# Callisto_Header_Test_Board_All_On.net
KiCad netlist of a schematic drawn in EAGLE
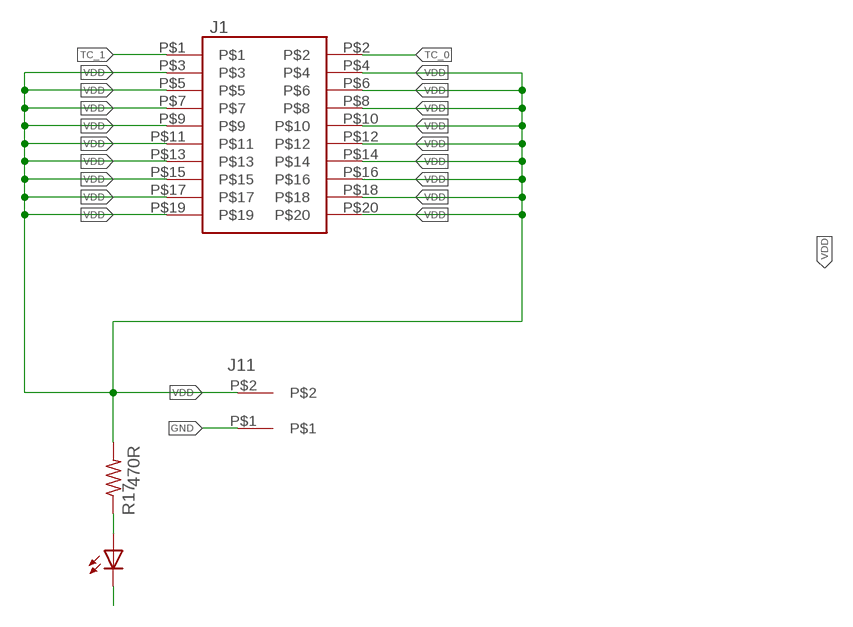
[diagram p0: schematic, sheet 1]

(export (version "E")
  (design (tool "Eeschema 10.0.6"))
  (components
    (comp (ref "J1")
      (value "20-pos")
      (footprint "eagle-import:2_X_10_.1_INCH")
      (fields (field (name "PARTNO") "67996-420HLF"))
      (libsource (lib "eagle-import") (part "2_X_10_HEADER_GENERIC"))
    )
    (comp (ref "J11")
      (value "2-pos")
      (footprint "eagle-import:2_3.81MM_PITCH")
      (fields (field (name "PARTNO") "691322310002"))
      (libsource (lib "eagle-import") (part "3.81MM_1_X_2_RT_ANGLE_PLUG_HEADER"))
    )
    (comp (ref "LED17")
      (value "Green")
      (footprint "eagle-import:0805")
      (fields (field (name "PARTNO") "LG R971-KN-1"))
      (libsource (lib "eagle-import") (part "LED_0805_GREEN"))
    )
    (comp (ref "R17")
      (value "470R")
      (footprint "eagle-import:0402")
      (libsource (lib "eagle-import") (part "R_0402"))
    )
  )
  (nets
    (net (code "1") (name "GND") (class "Default")
      (node (ref "J11") (pin "P$1") (pinfunction "P$1_P$1") (pintype "bidirectional"))
      (node (ref "LED17") (pin "2") (pinfunction "C_2") (pintype "passive"))
    )
    (net (code "2") (name "Net-(LED17-A)") (class "Default")
      (node (ref "LED17") (pin "1") (pinfunction "A_1") (pintype "passive"))
      (node (ref "R17") (pin "P$1") (pinfunction "1_P$1") (pintype "passive"))
    )
    (net (code "3") (name "TC_0") (class "Default")
      (node (ref "J1") (pin "P$2") (pinfunction "P$2_P$2") (pintype "bidirectional"))
    )
    (net (code "4") (name "TC_1") (class "Default")
      (node (ref "J1") (pin "P$1") (pinfunction "P$1_P$1") (pintype "bidirectional"))
    )
    (net (code "5") (name "VDD") (class "Default")
      (node (ref "J1") (pin "P$10") (pinfunction "P$10_P$10") (pintype "bidirectional"))
      (node (ref "J1") (pin "P$11") (pinfunction "P$11_P$11") (pintype "bidirectional"))
      (node (ref "J1") (pin "P$12") (pinfunction "P$12_P$12") (pintype "bidirectional"))
      (node (ref "J1") (pin "P$13") (pinfunction "P$13_P$13") (pintype "bidirectional"))
      (node (ref "J1") (pin "P$14") (pinfunction "P$14_P$14") (pintype "bidirectional"))
      (node (ref "J1") (pin "P$15") (pinfunction "P$15_P$15") (pintype "bidirectional"))
      (node (ref "J1") (pin "P$16") (pinfunction "P$16_P$16") (pintype "bidirectional"))
      (node (ref "J1") (pin "P$17") (pinfunction "P$17_P$17") (pintype "bidirectional"))
      (node (ref "J1") (pin "P$18") (pinfunction "P$18_P$18") (pintype "bidirectional"))
      (node (ref "J1") (pin "P$19") (pinfunction "P$19_P$19") (pintype "bidirectional"))
      (node (ref "J1") (pin "P$20") (pinfunction "P$20_P$20") (pintype "bidirectional"))
      (node (ref "J1") (pin "P$3") (pinfunction "P$3_P$3") (pintype "bidirectional"))
      (node (ref "J1") (pin "P$4") (pinfunction "P$4_P$4") (pintype "bidirectional"))
      (node (ref "J1") (pin "P$5") (pinfunction "P$5_P$5") (pintype "bidirectional"))
      (node (ref "J1") (pin "P$6") (pinfunction "P$6_P$6") (pintype "bidirectional"))
      (node (ref "J1") (pin "P$7") (pinfunction "P$7_P$7") (pintype "bidirectional"))
      (node (ref "J1") (pin "P$8") (pinfunction "P$8_P$8") (pintype "bidirectional"))
      (node (ref "J1") (pin "P$9") (pinfunction "P$9_P$9") (pintype "bidirectional"))
      (node (ref "J11") (pin "P$2") (pinfunction "P$2_P$2") (pintype "bidirectional"))
      (node (ref "R17") (pin "P$2") (pinfunction "2_P$2") (pintype "passive"))
    )
  )
)
